# 800U-R3N3_LED_V1_2.net
KiCad netlist of a schematic drawn in Altium Designer
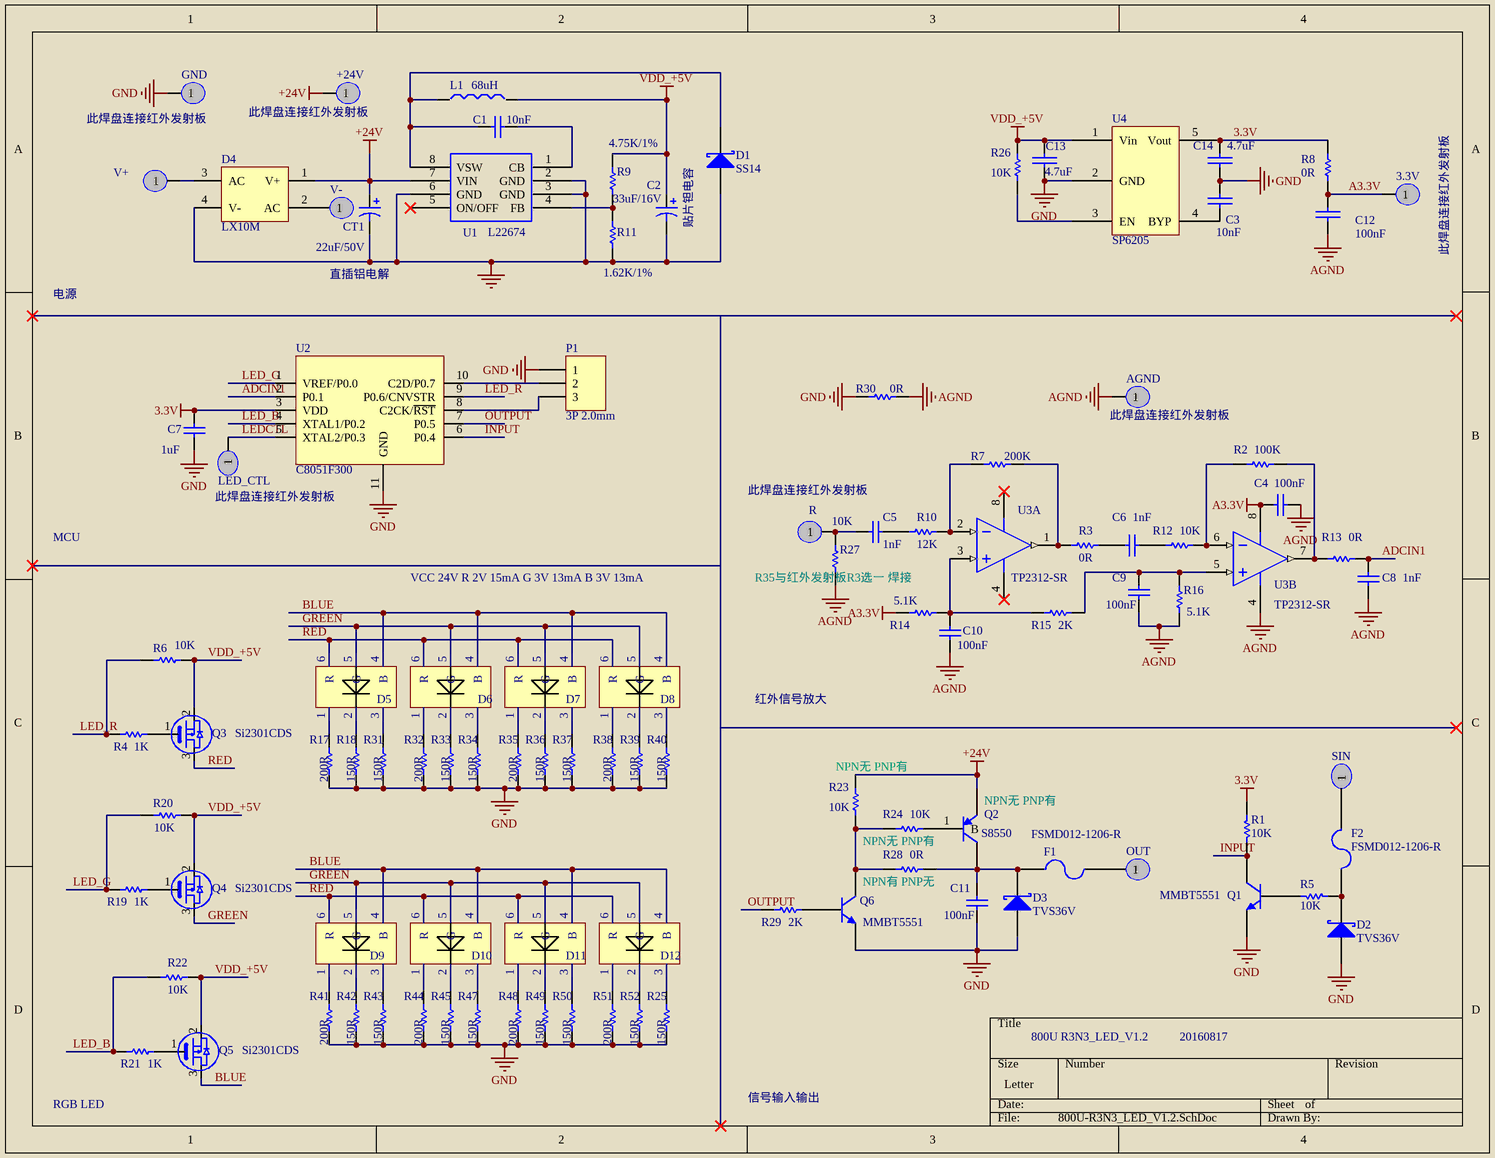
[diagram p0: 800U-R3N3_LED_V1.2.SchDoc]

(export (version "E")
  (design (tool "Eeschema 10.0.6"))
  (components
    (comp (ref "+24V")
      (value "~")
      (footprint "HOLE_SMD")
      (fields (field (name "ALTIUM_UNNAMED_1") "此焊盘连接红外发射板"))
      (libsource (lib "MODBUS_V1.0") (part "焊盘"))
    )
    (comp (ref "3.3V")
      (value "~")
      (footprint "HOLE_SMD")
      (fields (field (name "ALTIUM_UNNAMED_1") "此焊盘连接红外发射板"))
      (libsource (lib "MODBUS_V1.0") (part "焊盘"))
    )
    (comp (ref "AGND")
      (value "~")
      (footprint "HOLE_SMD")
      (fields (field (name "ALTIUM_UNNAMED_1") "此焊盘连接红外发射板"))
      (libsource (lib "MODBUS_V1.0") (part "焊盘"))
    )
    (comp (ref "C1")
      (value "10nF")
      (footprint "C0603")
      (description "Capacitor")
      (fields (field (name "PUBLISHER") "Altium Limited"))
      (libsource (lib "*") (part "Cap"))
    )
    (comp (ref "C2")
      (value "33uF/16V")
      (footprint "CT3528")
      (description "Polarized Capacitor (Radial)")
      (fields (field (name "KIND") "贴片钽电容"))
      (libsource (lib "*") (part "Cap Pol1"))
    )
    (comp (ref "C3")
      (value "10nF")
      (footprint "C0603")
      (description "Capacitor")
      (libsource (lib "*") (part "CAP"))
    )
    (comp (ref "C4")
      (value "100nF")
      (footprint "C0603")
      (description "Capacitor")
      (fields (field (name "PUBLISHER") "Altium Limited"))
      (libsource (lib "TMJD1.0") (part "Cap"))
    )
    (comp (ref "C5")
      (value "1nF")
      (footprint "C0603")
      (description "Capacitor")
      (fields (field (name "PUBLISHER") "Altium Limited"))
      (libsource (lib "TMJD1.0") (part "Cap"))
    )
    (comp (ref "C6")
      (value "1nF")
      (footprint "C0603")
      (description "Capacitor")
      (fields (field (name "PUBLISHER") "Altium Limited"))
      (libsource (lib "TMJD1.0") (part "Cap"))
    )
    (comp (ref "C7")
      (value "1uF")
      (footprint "C0603")
      (description "贴片电容")
      (fields (field (name "PUBLISHER") "Altium Limited"))
      (libsource (lib "TMJD1.0") (part "Cap"))
    )
    (comp (ref "C8")
      (value "1nF")
      (footprint "C0603")
      (description "Capacitor")
      (fields (field (name "PUBLISHER") "Altium Limited"))
      (libsource (lib "TMJD1.0") (part "Cap"))
    )
    (comp (ref "C9")
      (value "100nF")
      (footprint "C0603")
      (description "Capacitor")
      (fields (field (name "PUBLISHER") "Altium Limited"))
      (libsource (lib "TMJD1.0") (part "Cap"))
    )
    (comp (ref "C10")
      (value "100nF")
      (footprint "C0603")
      (description "Capacitor")
      (fields (field (name "PUBLISHER") "Altium Limited"))
      (libsource (lib "TMJD1.0") (part "Cap"))
    )
    (comp (ref "C11")
      (value "100nF")
      (footprint "C0603")
      (description "贴片电容")
      (fields (field (name "PUBLISHER") "Altium Limited"))
      (libsource (lib "TMJD1.0") (part "Cap"))
    )
    (comp (ref "C12")
      (value "100nF")
      (footprint "C0603")
      (description "Capacitor")
      (libsource (lib "*") (part "CAP"))
    )
    (comp (ref "C13")
      (value "4.7uF")
      (footprint "C0603")
      (description "Capacitor")
      (libsource (lib "*") (part "CAP"))
    )
    (comp (ref "C14")
      (value "4.7uF")
      (footprint "C0603")
      (description "Capacitor")
      (libsource (lib "*") (part "CAP"))
    )
    (comp (ref "CT1")
      (value "22uF/50V")
      (footprint "RB0.1")
      (description "Polarized Capacitor (Radial)")
      (fields (field (name "KIND") "直插铝电解"))
      (libsource (lib "*") (part "Cap Pol1"))
    )
    (comp (ref "D1") (value "SS14") (footprint "SMB") (libsource (lib "*") (part "SMBJ6.0CA")))
    (comp (ref "D2")
      (value "TVS36V")
      (footprint "HSMA")
      (description "贴片TVS")
      (fields (field (name "PUBLISHER") "Altium Limited"))
      (libsource (lib "*") (part "D Schottky"))
    )
    (comp (ref "D3")
      (value "TVS36V")
      (footprint "HSMA")
      (description "贴片TVS")
      (fields (field (name "PUBLISHER") "Altium Limited"))
      (libsource (lib "*") (part "D Schottky"))
    )
    (comp (ref "D4")
      (value "LX10M")
      (footprint "桥堆 3.8*3.5")
      (description "贴片桥堆")
      (libsource (lib "Miscellaneous Devices") (part "Bridge2"))
    )
    (comp (ref "D5")
      (value "5050RGB")
      (footprint "5050RGB")
      (description "RBG发光管")
      (libsource (lib "MODBUS_V1.0") (part "5050RGB"))
    )
    (comp (ref "D6")
      (value "5050RGB")
      (footprint "5050RGB")
      (description "RBG发光管")
      (libsource (lib "MODBUS_V1.0") (part "5050RGB"))
    )
    (comp (ref "D7")
      (value "5050RGB")
      (footprint "5050RGB")
      (description "RBG发光管")
      (libsource (lib "MODBUS_V1.0") (part "5050RGB"))
    )
    (comp (ref "D8")
      (value "5050RGB")
      (footprint "5050RGB")
      (description "RBG发光管")
      (libsource (lib "MODBUS_V1.0") (part "5050RGB"))
    )
    (comp (ref "D9")
      (value "5050RGB")
      (footprint "5050RGB")
      (description "RBG发光管")
      (libsource (lib "MODBUS_V1.0") (part "5050RGB"))
    )
    (comp (ref "D10")
      (value "5050RGB")
      (footprint "5050RGB")
      (description "RBG发光管")
      (libsource (lib "MODBUS_V1.0") (part "5050RGB"))
    )
    (comp (ref "D11")
      (value "5050RGB")
      (footprint "5050RGB")
      (description "RBG发光管")
      (libsource (lib "MODBUS_V1.0") (part "5050RGB"))
    )
    (comp (ref "D12")
      (value "5050RGB")
      (footprint "5050RGB")
      (description "RBG发光管")
      (libsource (lib "MODBUS_V1.0") (part "5050RGB"))
    )
    (comp (ref "F1")
      (value "FSMD012-1206-R")
      (footprint "1206")
      (description "Fuse")
      (libsource (lib "Miscellaneous Devices") (part "Fuse 2"))
    )
    (comp (ref "F2")
      (value "FSMD012-1206-R")
      (footprint "1206")
      (description "Fuse")
      (libsource (lib "") (part "Fuse 2_1"))
    )
    (comp (ref "GND")
      (value "~")
      (footprint "HOLE_SMD")
      (fields (field (name "ALTIUM_UNNAMED_1") "此焊盘连接红外发射板"))
      (libsource (lib "MODBUS_V1.0") (part "焊盘"))
    )
    (comp (ref "L1") (value "68uH") (footprint "L-6X6") (libsource (lib "*") (part "电感")))
    (comp (ref "LED_CTL")
      (value "~")
      (footprint "HOLE_SMD")
      (fields (field (name "ALTIUM_UNNAMED_1") "此焊盘连接红外发射板"))
      (libsource (lib "MODBUS_V1.0") (part "焊盘"))
    )
    (comp (ref "OUT") (value "~") (footprint "HOLE_SMD") (libsource (lib "MODBUS_V1.0") (part "焊盘")))
    (comp (ref "P1")
      (value "3P 2.0mm")
      (footprint "SIP3")
      (description "插座")
      (fields (field (name "PUBLISHER") "Altium Limited"))
      (libsource (lib "Miscellaneous Connectors") (part "MHDR1X3"))
    )
    (comp (ref "Q1")
      (value "MMBT5551")
      (footprint "SOT-23")
      (description "贴片NPN三极管")
      (libsource (lib "Miscellaneous Devices") (part "NPN"))
    )
    (comp (ref "Q2")
      (value "S8550")
      (footprint "SOT-23")
      (description "贴片PNP三极管")
      (fields (field (name "ALTIUM_UNNAMED_1") "NPN无 PNP有"))
      (libsource (lib "MODBUS_V1.0") (part "S8550"))
    )
    (comp (ref "Q3")
      (value "Si2301CDS")
      (footprint "SOT-23")
      (description "贴片MOS管")
      (libsource (lib "BATTERY") (part "P-MOSFET"))
    )
    (comp (ref "Q4")
      (value "Si2301CDS")
      (footprint "SOT-23")
      (description "贴片MOS管")
      (libsource (lib "BATTERY") (part "P-MOSFET"))
    )
    (comp (ref "Q5")
      (value "Si2301CDS")
      (footprint "SOT-23")
      (description "贴片MOS管")
      (libsource (lib "BATTERY") (part "P-MOSFET"))
    )
    (comp (ref "Q6")
      (value "MMBT5551")
      (footprint "SOT-23")
      (description "NPN三极管")
      (libsource (lib "Miscellaneous Devices") (part "NPN"))
    )
    (comp (ref "R")
      (value "~")
      (footprint "HOLE_SMD")
      (fields (field (name "ALTIUM_UNNAMED_1") "此焊盘连接红外发射板"))
      (libsource (lib "MODBUS_V1.0") (part "焊盘"))
    )
    (comp (ref "R1")
      (value "10K")
      (footprint "R0603")
      (description "贴片电阻")
      (libsource (lib "Miscellaneous Devices") (part "Res Semi"))
    )
    (comp (ref "R2")
      (value "100K")
      (footprint "R0603")
      (description "Semiconductor Resistor")
      (libsource (lib "Miscellaneous Devices") (part "Res Semi"))
    )
    (comp (ref "R3")
      (value "0R")
      (footprint "R0603")
      (description "Semiconductor Resistor")
      (libsource (lib "Miscellaneous Devices") (part "Res Semi"))
    )
    (comp (ref "R4")
      (value "1K")
      (footprint "R0603")
      (description "贴片电阻")
      (libsource (lib "Miscellaneous Devices") (part "Res Semi"))
    )
    (comp (ref "R5")
      (value "10K")
      (footprint "R0603")
      (description "贴片电阻")
      (libsource (lib "Miscellaneous Devices") (part "Res Semi"))
    )
    (comp (ref "R6")
      (value "10K")
      (footprint "R0603")
      (description "贴片电阻")
      (libsource (lib "Miscellaneous Devices") (part "Res Semi"))
    )
    (comp (ref "R7")
      (value "200K")
      (footprint "R0603")
      (description "Semiconductor Resistor")
      (libsource (lib "Miscellaneous Devices") (part "Res Semi"))
    )
    (comp (ref "R8")
      (value "0R")
      (footprint "R0603")
      (description "Resistor")
      (fields (field (name "PUBLISHER") "Altium Limited"))
      (libsource (lib "*") (part "Res1"))
    )
    (comp (ref "R9")
      (value "4.75K/1%")
      (footprint "R0603")
      (description "Semiconductor Resistor")
      (fields (field (name "PUBLISHER") "Altium Limited"))
      (libsource (lib "*") (part "Res Semi"))
    )
    (comp (ref "R10")
      (value "12K")
      (footprint "R0603")
      (description "Semiconductor Resistor")
      (libsource (lib "Miscellaneous Devices") (part "Res Semi"))
    )
    (comp (ref "R11")
      (value "1.62K/1%")
      (footprint "R0603")
      (description "Semiconductor Resistor")
      (fields (field (name "PUBLISHER") "Altium Limited"))
      (libsource (lib "*") (part "Res Semi"))
    )
    (comp (ref "R12")
      (value "10K")
      (footprint "R0603")
      (description "Semiconductor Resistor")
      (libsource (lib "Miscellaneous Devices") (part "Res Semi"))
    )
    (comp (ref "R13")
      (value "0R")
      (footprint "R0603")
      (description "Semiconductor Resistor")
      (libsource (lib "Miscellaneous Devices") (part "Res Semi"))
    )
    (comp (ref "R14")
      (value "5.1K")
      (footprint "R0603")
      (description "Semiconductor Resistor")
      (libsource (lib "Miscellaneous Devices") (part "Res Semi"))
    )
    (comp (ref "R15")
      (value "2K")
      (footprint "R0603")
      (description "Semiconductor Resistor")
      (libsource (lib "Miscellaneous Devices") (part "Res Semi"))
    )
    (comp (ref "R16")
      (value "5.1K")
      (footprint "R0603")
      (description "Semiconductor Resistor")
      (libsource (lib "Miscellaneous Devices") (part "Res Semi"))
    )
    (comp (ref "R17")
      (value "200R")
      (footprint "0805")
      (description "贴片电阻")
      (libsource (lib "Miscellaneous Devices") (part "Res Semi"))
    )
    (comp (ref "R18")
      (value "150R")
      (footprint "0805")
      (description "贴片电阻")
      (libsource (lib "Miscellaneous Devices") (part "Res Semi"))
    )
    (comp (ref "R19")
      (value "1K")
      (footprint "R0603")
      (description "贴片电阻")
      (libsource (lib "Miscellaneous Devices") (part "Res Semi"))
    )
    (comp (ref "R20")
      (value "10K")
      (footprint "R0603")
      (description "贴片电阻")
      (libsource (lib "Miscellaneous Devices") (part "Res Semi"))
    )
    (comp (ref "R21")
      (value "1K")
      (footprint "R0603")
      (description "贴片电阻")
      (libsource (lib "Miscellaneous Devices") (part "Res Semi"))
    )
    (comp (ref "R22")
      (value "10K")
      (footprint "R0603")
      (description "贴片电阻")
      (libsource (lib "Miscellaneous Devices") (part "Res Semi"))
    )
    (comp (ref "R23")
      (value "10K")
      (footprint "R0603")
      (description "贴片电阻")
      (fields (field (name "ALTIUM_UNNAMED_1") "NPN无 PNP有"))
      (libsource (lib "Miscellaneous Devices") (part "Res Semi"))
    )
    (comp (ref "R24")
      (value "10K")
      (footprint "R0603")
      (description "贴片电阻")
      (fields (field (name "ALTIUM_UNNAMED_1") "NPN无 PNP有"))
      (libsource (lib "Miscellaneous Devices") (part "Res Semi"))
    )
    (comp (ref "R25")
      (value "150R")
      (footprint "0805")
      (description "贴片电阻")
      (libsource (lib "Miscellaneous Devices") (part "Res Semi"))
    )
    (comp (ref "R26")
      (value "10K")
      (footprint "R0603")
      (description "Resistor")
      (fields (field (name "PUBLISHER") "Altium Limited"))
      (libsource (lib "*") (part "Res1"))
    )
    (comp (ref "R27")
      (value "10K")
      (footprint "R0603")
      (description "Semiconductor Resistor")
      (fields (field (name "ALTIUM_UNNAMED_1") "R35与红外发射板R3选一 焊接"))
      (libsource (lib "Miscellaneous Devices") (part "Res Semi"))
    )
    (comp (ref "R28")
      (value "0R")
      (footprint "R0603")
      (description "贴片电阻")
      (fields (field (name "ALTIUM_UNNAMED_1") "NPN有 PNP无"))
      (libsource (lib "Miscellaneous Devices") (part "Res Semi"))
    )
    (comp (ref "R29")
      (value "2K")
      (footprint "R0603")
      (description "贴片电阻")
      (libsource (lib "Miscellaneous Devices") (part "Res Semi"))
    )
    (comp (ref "R30")
      (value "0R")
      (footprint "R0603")
      (description "Semiconductor Resistor")
      (libsource (lib "Miscellaneous Devices") (part "Res Semi"))
    )
    (comp (ref "R31")
      (value "150R")
      (footprint "0805")
      (description "贴片电阻")
      (libsource (lib "Miscellaneous Devices") (part "Res Semi"))
    )
    (comp (ref "R32")
      (value "200R")
      (footprint "0805")
      (description "贴片电阻")
      (libsource (lib "Miscellaneous Devices") (part "Res Semi"))
    )
    (comp (ref "R33")
      (value "150R")
      (footprint "0805")
      (description "贴片电阻")
      (libsource (lib "Miscellaneous Devices") (part "Res Semi"))
    )
    (comp (ref "R34")
      (value "150R")
      (footprint "0805")
      (description "贴片电阻")
      (libsource (lib "Miscellaneous Devices") (part "Res Semi"))
    )
    (comp (ref "R35")
      (value "200R")
      (footprint "0805")
      (description "贴片电阻")
      (libsource (lib "Miscellaneous Devices") (part "Res Semi"))
    )
    (comp (ref "R36")
      (value "150R")
      (footprint "0805")
      (description "贴片电阻")
      (libsource (lib "Miscellaneous Devices") (part "Res Semi"))
    )
    (comp (ref "R37")
      (value "150R")
      (footprint "0805")
      (description "贴片电阻")
      (libsource (lib "Miscellaneous Devices") (part "Res Semi"))
    )
    (comp (ref "R38")
      (value "200R")
      (footprint "0805")
      (description "贴片电阻")
      (libsource (lib "Miscellaneous Devices") (part "Res Semi"))
    )
    (comp (ref "R39")
      (value "150R")
      (footprint "0805")
      (description "贴片电阻")
      (libsource (lib "Miscellaneous Devices") (part "Res Semi"))
    )
    (comp (ref "R40")
      (value "150R")
      (footprint "0805")
      (description "贴片电阻")
      (libsource (lib "Miscellaneous Devices") (part "Res Semi"))
    )
    (comp (ref "R41")
      (value "200R")
      (footprint "MODBUS_V2.0:0805")
      (description "贴片电阻")
      (libsource (lib "Miscellaneous Devices") (part "Res Semi"))
    )
    (comp (ref "R42")
      (value "150R")
      (footprint "0805")
      (description "贴片电阻")
      (libsource (lib "Miscellaneous Devices") (part "Res Semi"))
    )
    (comp (ref "R43")
      (value "150R")
      (footprint "0805")
      (description "贴片电阻")
      (libsource (lib "Miscellaneous Devices") (part "Res Semi"))
    )
    (comp (ref "R44")
      (value "200R")
      (footprint "0805")
      (description "贴片电阻")
      (libsource (lib "Miscellaneous Devices") (part "Res Semi"))
    )
    (comp (ref "R45")
      (value "150R")
      (footprint "0805")
      (description "贴片电阻")
      (libsource (lib "Miscellaneous Devices") (part "Res Semi"))
    )
    (comp (ref "R47")
      (value "150R")
      (footprint "0805")
      (description "贴片电阻")
      (libsource (lib "Miscellaneous Devices") (part "Res Semi"))
    )
    (comp (ref "R48")
      (value "200R")
      (footprint "0805")
      (description "贴片电阻")
      (libsource (lib "Miscellaneous Devices") (part "Res Semi"))
    )
    (comp (ref "R49")
      (value "150R")
      (footprint "0805")
      (description "贴片电阻")
      (libsource (lib "Miscellaneous Devices") (part "Res Semi"))
    )
    (comp (ref "R50")
      (value "150R")
      (footprint "0805")
      (description "贴片电阻")
      (libsource (lib "Miscellaneous Devices") (part "Res Semi"))
    )
    (comp (ref "R51")
      (value "200R")
      (footprint "0805")
      (description "贴片电阻")
      (libsource (lib "Miscellaneous Devices") (part "Res Semi"))
    )
    (comp (ref "R52")
      (value "150R")
      (footprint "0805")
      (description "贴片电阻")
      (libsource (lib "Miscellaneous Devices") (part "Res Semi"))
    )
    (comp (ref "SIN") (value "~") (footprint "HOLE_SMD") (libsource (lib "MODBUS_V1.0") (part "焊盘")))
    (comp (ref "U1") (value "L22674") (footprint "SO-1.27-9/4.0") (libsource (lib "*") (part "2674")))
    (comp (ref "U2")
      (value "C8051F300")
      (footprint "QFN-11")
      (description "贴片芯片")
      (libsource (lib "集成块") (part "PIC16C505"))
    )
    (comp (ref "U3")
      (value "TP2312-SR")
      (footprint "SO-8")
      (description "Dual Low Noise, Audio Amplifier")
      (fields (field (name "PUBLISHER") "Altium Limited"))
      (libsource (lib "Motorola Amplifier Audio Amplifier") (part "LM833D"))
    )
    (comp (ref "U4")
      (value "SP6205")
      (footprint "SOT-23-5")
      (libsource (lib "MODBUS_V1.0") (part "SP6203/SP6205"))
    )
    (comp (ref "V+") (value "~") (footprint "HOLE_SMD") (libsource (lib "MODBUS_V1.0") (part "焊盘")))
    (comp (ref "V-") (value "~") (footprint "HOLE_SMD") (libsource (lib "MODBUS_V1.0") (part "焊盘")))
  )
  (nets
    (net (code "1") (name "+24V") (class "Default")
      (node (ref "+24V") (pin "1") (pinfunction "1_1") (pintype "passive"))
      (node (ref "CT1") (pin "1") (pinfunction "1_1") (pintype "passive"))
      (node (ref "D4") (pin "1") (pinfunction "V+_1") (pintype "passive"))
      (node (ref "Q2") (pin "2") (pinfunction "E_2") (pintype "passive"))
      (node (ref "R23") (pin "2") (pinfunction "2_2") (pintype "passive"))
      (node (ref "U1") (pin "7") (pinfunction "VIN_7") (pintype "passive"))
    )
    (net (code "2") (name "/ADCIN1") (class "Default")
      (node (ref "C8") (pin "2") (pinfunction "2_2") (pintype "passive"))
      (node (ref "R13") (pin "2") (pinfunction "2_2") (pintype "passive"))
      (node (ref "U2") (pin "2") (pinfunction "P0.1_2") (pintype "passive"))
    )
    (net (code "3") (name "/BLUE") (class "Default")
      (node (ref "D10") (pin "4") (pinfunction "B_4") (pintype "passive"))
      (node (ref "D11") (pin "4") (pinfunction "B_4") (pintype "passive"))
      (node (ref "D12") (pin "4") (pinfunction "B_4") (pintype "passive"))
      (node (ref "D5") (pin "4") (pinfunction "B_4") (pintype "passive"))
      (node (ref "D6") (pin "4") (pinfunction "B_4") (pintype "passive"))
      (node (ref "D7") (pin "4") (pinfunction "B_4") (pintype "passive"))
      (node (ref "D8") (pin "4") (pinfunction "B_4") (pintype "passive"))
      (node (ref "D9") (pin "4") (pinfunction "B_4") (pintype "passive"))
      (node (ref "Q5") (pin "3") (pinfunction "D_3") (pintype "passive"))
    )
    (net (code "4") (name "/GREEN") (class "Default")
      (node (ref "D10") (pin "5") (pinfunction "G_5") (pintype "passive"))
      (node (ref "D11") (pin "5") (pinfunction "G_5") (pintype "passive"))
      (node (ref "D12") (pin "5") (pinfunction "G_5") (pintype "passive"))
      (node (ref "D5") (pin "5") (pinfunction "G_5") (pintype "passive"))
      (node (ref "D6") (pin "5") (pinfunction "G_5") (pintype "passive"))
      (node (ref "D7") (pin "5") (pinfunction "G_5") (pintype "passive"))
      (node (ref "D8") (pin "5") (pinfunction "G_5") (pintype "passive"))
      (node (ref "D9") (pin "5") (pinfunction "G_5") (pintype "passive"))
      (node (ref "Q4") (pin "3") (pinfunction "D_3") (pintype "passive"))
    )
    (net (code "5") (name "/INPUT") (class "Default")
      (node (ref "Q1") (pin "3") (pinfunction "C_3") (pintype "passive"))
      (node (ref "R1") (pin "1") (pinfunction "1_1") (pintype "passive"))
      (node (ref "U2") (pin "6") (pinfunction "P0.4_6") (pintype "passive"))
    )
    (net (code "6") (name "/LEDCTL") (class "Default")
      (node (ref "LED_CTL") (pin "1") (pinfunction "1_1") (pintype "passive"))
      (node (ref "U2") (pin "5") (pinfunction "XTAL2/P0.3_5") (pintype "passive"))
    )
    (net (code "7") (name "/LED_B") (class "Default")
      (node (ref "R21") (pin "2") (pinfunction "2_2") (pintype "passive"))
      (node (ref "R22") (pin "2") (pinfunction "2_2") (pintype "passive"))
      (node (ref "U2") (pin "4") (pinfunction "XTAL1/P0.2_4") (pintype "passive"))
    )
    (net (code "8") (name "/LED_G") (class "Default")
      (node (ref "R19") (pin "2") (pinfunction "2_2") (pintype "passive"))
      (node (ref "R20") (pin "2") (pinfunction "2_2") (pintype "passive"))
      (node (ref "U2") (pin "1") (pinfunction "VREF/P0.0_1") (pintype "passive"))
    )
    (net (code "9") (name "/LED_R") (class "Default")
      (node (ref "R4") (pin "2") (pinfunction "2_2") (pintype "passive"))
      (node (ref "R6") (pin "2") (pinfunction "2_2") (pintype "passive"))
      (node (ref "U2") (pin "9") (pinfunction "P0.6/CNVSTR_9") (pintype "passive"))
    )
    (net (code "10") (name "/OUTPUT") (class "Default")
      (node (ref "R29") (pin "2") (pinfunction "2_2") (pintype "passive"))
      (node (ref "U2") (pin "7") (pinfunction "P0.5_7") (pintype "passive"))
    )
    (net (code "11") (name "/RED") (class "Default")
      (node (ref "D10") (pin "6") (pinfunction "R_6") (pintype "passive"))
      (node (ref "D11") (pin "6") (pinfunction "R_6") (pintype "passive"))
      (node (ref "D12") (pin "6") (pinfunction "R_6") (pintype "passive"))
      (node (ref "D5") (pin "6") (pinfunction "R_6") (pintype "passive"))
      (node (ref "D6") (pin "6") (pinfunction "R_6") (pintype "passive"))
      (node (ref "D7") (pin "6") (pinfunction "R_6") (pintype "passive"))
      (node (ref "D8") (pin "6") (pinfunction "R_6") (pintype "passive"))
      (node (ref "D9") (pin "6") (pinfunction "R_6") (pintype "passive"))
      (node (ref "Q3") (pin "3") (pinfunction "D_3") (pintype "passive"))
    )
    (net (code "12") (name "3.3V") (class "Default")
      (node (ref "C14") (pin "1") (pinfunction "1_1") (pintype "passive"))
      (node (ref "C7") (pin "1") (pinfunction "1_1") (pintype "passive"))
      (node (ref "R1") (pin "2") (pinfunction "2_2") (pintype "passive"))
      (node (ref "R8") (pin "1") (pinfunction "1_1") (pintype "passive"))
      (node (ref "U2") (pin "3") (pinfunction "VDD_3") (pintype "passive"))
      (node (ref "U4") (pin "5") (pinfunction "Vout_5") (pintype "passive"))
    )
    (net (code "13") (name "A3.3V") (class "Default")
      (node (ref "3.3V") (pin "1") (pinfunction "1_1") (pintype "passive"))
      (node (ref "C12") (pin "2") (pinfunction "2_2") (pintype "passive"))
      (node (ref "C4") (pin "1") (pinfunction "1_1") (pintype "passive"))
      (node (ref "R14") (pin "1") (pinfunction "1_1") (pintype "passive"))
      (node (ref "R8") (pin "2") (pinfunction "2_2") (pintype "passive"))
      (node (ref "U3") (pin "8") (pinfunction "VCC_8") (pintype "power_in"))
    )
    (net (code "14") (name "AGND") (class "Default")
      (node (ref "AGND") (pin "1") (pinfunction "1_1") (pintype "passive"))
      (node (ref "C10") (pin "2") (pinfunction "2_2") (pintype "passive"))
      (node (ref "C12") (pin "1") (pinfunction "1_1") (pintype "passive"))
      (node (ref "C4") (pin "2") (pinfunction "2_2") (pintype "passive"))
      (node (ref "C8") (pin "1") (pinfunction "1_1") (pintype "passive"))
      (node (ref "C9") (pin "2") (pinfunction "2_2") (pintype "passive"))
      (node (ref "R16") (pin "1") (pinfunction "1_1") (pintype "passive"))
      (node (ref "R27") (pin "2") (pinfunction "2_2") (pintype "passive"))
      (node (ref "R30") (pin "2") (pinfunction "2_2") (pintype "passive"))
      (node (ref "U3") (pin "4") (pinfunction "VEE_4") (pintype "power_in"))
    )
    (net (code "15") (name "GND") (class "Default")
      (node (ref "C11") (pin "2") (pinfunction "2_2") (pintype "passive"))
      (node (ref "C13") (pin "2") (pinfunction "2_2") (pintype "passive"))
      (node (ref "C14") (pin "2") (pinfunction "2_2") (pintype "passive"))
      (node (ref "C2") (pin "2") (pinfunction "2_2") (pintype "passive"))
      (node (ref "C3") (pin "2") (pinfunction "2_2") (pintype "passive"))
      (node (ref "C7") (pin "2") (pinfunction "2_2") (pintype "passive"))
      (node (ref "CT1") (pin "2") (pinfunction "2_2") (pintype "passive"))
      (node (ref "D1") (pin "1") (pinfunction "A_1") (pintype "passive"))
      (node (ref "D2") (pin "1") (pinfunction "A_1") (pintype "passive"))
      (node (ref "D3") (pin "1") (pinfunction "A_1") (pintype "passive"))
      (node (ref "D4") (pin "4") (pinfunction "V-_4") (pintype "passive"))
      (node (ref "GND") (pin "1") (pinfunction "1_1") (pintype "passive"))
      (node (ref "P1") (pin "1") (pinfunction "1_1") (pintype "passive"))
      (node (ref "Q1") (pin "2") (pinfunction "E_2") (pintype "passive"))
      (node (ref "Q6") (pin "2") (pinfunction "E_2") (pintype "passive"))
      (node (ref "R11") (pin "1") (pinfunction "1_1") (pintype "passive"))
      (node (ref "R17") (pin "1") (pinfunction "1_1") (pintype "passive"))
      (node (ref "R18") (pin "1") (pinfunction "1_1") (pintype "passive"))
      (node (ref "R25") (pin "1") (pinfunction "1_1") (pintype "passive"))
      (node (ref "R30") (pin "1") (pinfunction "1_1") (pintype "passive"))
      (node (ref "R31") (pin "1") (pinfunction "1_1") (pintype "passive"))
      (node (ref "R32") (pin "1") (pinfunction "1_1") (pintype "passive"))
      (node (ref "R33") (pin "1") (pinfunction "1_1") (pintype "passive"))
      (node (ref "R34") (pin "1") (pinfunction "1_1") (pintype "passive"))
      (node (ref "R35") (pin "1") (pinfunction "1_1") (pintype "passive"))
      (node (ref "R36") (pin "1") (pinfunction "1_1") (pintype "passive"))
      (node (ref "R37") (pin "1") (pinfunction "1_1") (pintype "passive"))
      (node (ref "R38") (pin "1") (pinfunction "1_1") (pintype "passive"))
      (node (ref "R39") (pin "1") (pinfunction "1_1") (pintype "passive"))
      (node (ref "R40") (pin "1") (pinfunction "1_1") (pintype "passive"))
      (node (ref "R41") (pin "1") (pinfunction "1_1") (pintype "passive"))
      (node (ref "R42") (pin "1") (pinfunction "1_1") (pintype "passive"))
      (node (ref "R43") (pin "1") (pinfunction "1_1") (pintype "passive"))
      (node (ref "R44") (pin "1") (pinfunction "1_1") (pintype "passive"))
      (node (ref "R45") (pin "1") (pinfunction "1_1") (pintype "passive"))
      (node (ref "R47") (pin "1") (pinfunction "1_1") (pintype "passive"))
      (node (ref "R48") (pin "1") (pinfunction "1_1") (pintype "passive"))
      (node (ref "R49") (pin "1") (pinfunction "1_1") (pintype "passive"))
      (node (ref "R50") (pin "1") (pinfunction "1_1") (pintype "passive"))
      (node (ref "R51") (pin "1") (pinfunction "1_1") (pintype "passive"))
      (node (ref "R52") (pin "1") (pinfunction "1_1") (pintype "passive"))
      (node (ref "U1") (pin "2") (pinfunction "GND_2") (pintype "passive"))
      (node (ref "U1") (pin "3") (pinfunction "GND_3") (pintype "passive"))
      (node (ref "U1") (pin "6") (pinfunction "GND_6") (pintype "passive"))
      (node (ref "U2") (pin "11") (pinfunction "GND_11") (pintype "passive"))
      (node (ref "U4") (pin "2") (pinfunction "GND_2") (pintype "passive"))
    )
    (net (code "16") (name "Net-(C5-Pad1)") (class "Default")
      (node (ref "C5") (pin "1") (pinfunction "1_1") (pintype "passive"))
      (node (ref "R") (pin "1") (pinfunction "1_1") (pintype "passive"))
      (node (ref "R27") (pin "1") (pinfunction "1_1") (pintype "passive"))
    )
    (net (code "17") (name "Net-(C5-Pad2)") (class "Default")
      (node (ref "C5") (pin "2") (pinfunction "2_2") (pintype "passive"))
      (node (ref "R10") (pin "1") (pinfunction "1_1") (pintype "passive"))
    )
    (net (code "18") (name "Net-(C6-Pad1)") (class "Default")
      (node (ref "C6") (pin "1") (pinfunction "1_1") (pintype "passive"))
      (node (ref "R3") (pin "2") (pinfunction "2_2") (pintype "passive"))
    )
    (net (code "19") (name "Net-(C6-Pad2)") (class "Default")
      (node (ref "C6") (pin "2") (pinfunction "2_2") (pintype "passive"))
      (node (ref "R12") (pin "1") (pinfunction "1_1") (pintype "passive"))
    )
    (net (code "20") (name "Net-(D1-K)") (class "Default")
      (node (ref "C1") (pin "2") (pinfunction "2_2") (pintype "passive"))
      (node (ref "D1") (pin "2") (pinfunction "K_2") (pintype "passive"))
      (node (ref "L1") (pin "1") (pinfunction "1_1") (pintype "passive"))
      (node (ref "U1") (pin "8") (pinfunction "VSW_8") (pintype "passive"))
    )
    (net (code "21") (name "Net-(D2-K)") (class "Default")
      (node (ref "D2") (pin "2") (pinfunction "K_2") (pintype "passive"))
      (node (ref "F2") (pin "1") (pinfunction "1_1") (pintype "passive"))
      (node (ref "R5") (pin "1") (pinfunction "1_1") (pintype "passive"))
    )
    (net (code "22") (name "Net-(D3-K)") (class "Default")
      (node (ref "C11") (pin "1") (pinfunction "1_1") (pintype "passive"))
      (node (ref "D3") (pin "2") (pinfunction "K_2") (pintype "passive"))
      (node (ref "F1") (pin "2") (pinfunction "2_2") (pintype "passive"))
      (node (ref "Q2") (pin "3") (pinfunction "C_3") (pintype "passive"))
      (node (ref "R28") (pin "2") (pinfunction "2_2") (pintype "passive"))
    )
    (net (code "23") (name "Net-(D4-AC-Pad2)") (class "Default")
      (node (ref "D4") (pin "2") (pinfunction "AC_2") (pintype "passive"))
      (node (ref "V-") (pin "1") (pinfunction "1_1") (pintype "passive"))
    )
    (net (code "24") (name "Net-(D4-AC-Pad3)") (class "Default")
      (node (ref "D4") (pin "3") (pinfunction "AC_3") (pintype "passive"))
      (node (ref "V+") (pin "1") (pinfunction "1_1") (pintype "passive"))
    )
    (net (code "25") (name "Net-(D5-Pad1)") (class "Default")
      (node (ref "D5") (pin "1") (pintype "passive"))
      (node (ref "R17") (pin "2") (pinfunction "2_2") (pintype "passive"))
    )
    (net (code "26") (name "Net-(D5-Pad2)") (class "Default")
      (node (ref "D5") (pin "2") (pintype "passive"))
      (node (ref "R18") (pin "2") (pinfunction "2_2") (pintype "passive"))
    )
    (net (code "27") (name "Net-(D5-Pad3)") (class "Default")
      (node (ref "D5") (pin "3") (pintype "passive"))
      (node (ref "R31") (pin "2") (pinfunction "2_2") (pintype "passive"))
    )
    (net (code "28") (name "Net-(D6-Pad1)") (class "Default")
      (node (ref "D6") (pin "1") (pintype "passive"))
      (node (ref "R32") (pin "2") (pinfunction "2_2") (pintype "passive"))
    )
    (net (code "29") (name "Net-(D6-Pad2)") (class "Default")
      (node (ref "D6") (pin "2") (pintype "passive"))
      (node (ref "R33") (pin "2") (pinfunction "2_2") (pintype "passive"))
    )
    (net (code "30") (name "Net-(D6-Pad3)") (class "Default")
      (node (ref "D6") (pin "3") (pintype "passive"))
      (node (ref "R34") (pin "2") (pinfunction "2_2") (pintype "passive"))
    )
    (net (code "31") (name "Net-(D7-Pad1)") (class "Default")
      (node (ref "D7") (pin "1") (pintype "passive"))
      (node (ref "R35") (pin "2") (pinfunction "2_2") (pintype "passive"))
    )
    (net (code "32") (name "Net-(D7-Pad2)") (class "Default")
      (node (ref "D7") (pin "2") (pintype "passive"))
      (node (ref "R36") (pin "2") (pinfunction "2_2") (pintype "passive"))
    )
    (net (code "33") (name "Net-(D7-Pad3)") (class "Default")
      (node (ref "D7") (pin "3") (pintype "passive"))
      (node (ref "R37") (pin "2") (pinfunction "2_2") (pintype "passive"))
    )
    (net (code "34") (name "Net-(D8-Pad1)") (class "Default")
      (node (ref "D8") (pin "1") (pintype "passive"))
      (node (ref "R38") (pin "2") (pinfunction "2_2") (pintype "passive"))
    )
    (net (code "35") (name "Net-(D8-Pad2)") (class "Default")
      (node (ref "D8") (pin "2") (pintype "passive"))
      (node (ref "R39") (pin "2") (pinfunction "2_2") (pintype "passive"))
    )
    (net (code "36") (name "Net-(D8-Pad3)") (class "Default")
      (node (ref "D8") (pin "3") (pintype "passive"))
      (node (ref "R40") (pin "2") (pinfunction "2_2") (pintype "passive"))
    )
    (net (code "37") (name "Net-(D9-Pad1)") (class "Default")
      (node (ref "D9") (pin "1") (pintype "passive"))
      (node (ref "R41") (pin "2") (pinfunction "2_2") (pintype "passive"))
    )
    (net (code "38") (name "Net-(D9-Pad2)") (class "Default")
      (node (ref "D9") (pin "2") (pintype "passive"))
      (node (ref "R42") (pin "2") (pinfunction "2_2") (pintype "passive"))
    )
    (net (code "39") (name "Net-(D9-Pad3)") (class "Default")
      (node (ref "D9") (pin "3") (pintype "passive"))
      (node (ref "R43") (pin "2") (pinfunction "2_2") (pintype "passive"))
    )
    (net (code "40") (name "Net-(D10-Pad1)") (class "Default")
      (node (ref "D10") (pin "1") (pintype "passive"))
      (node (ref "R44") (pin "2") (pinfunction "2_2") (pintype "passive"))
    )
    (net (code "41") (name "Net-(D10-Pad2)") (class "Default")
      (node (ref "D10") (pin "2") (pintype "passive"))
      (node (ref "R45") (pin "2") (pinfunction "2_2") (pintype "passive"))
    )
    (net (code "42") (name "Net-(D10-Pad3)") (class "Default")
      (node (ref "D10") (pin "3") (pintype "passive"))
      (node (ref "R47") (pin "2") (pinfunction "2_2") (pintype "passive"))
    )
    (net (code "43") (name "Net-(D11-Pad1)") (class "Default")
      (node (ref "D11") (pin "1") (pintype "passive"))
      (node (ref "R48") (pin "2") (pinfunction "2_2") (pintype "passive"))
    )
    (net (code "44") (name "Net-(D11-Pad2)") (class "Default")
      (node (ref "D11") (pin "2") (pintype "passive"))
      (node (ref "R49") (pin "2") (pinfunction "2_2") (pintype "passive"))
    )
    (net (code "45") (name "Net-(D11-Pad3)") (class "Default")
      (node (ref "D11") (pin "3") (pintype "passive"))
      (node (ref "R50") (pin "2") (pinfunction "2_2") (pintype "passive"))
    )
    (net (code "46") (name "Net-(D12-Pad1)") (class "Default")
      (node (ref "D12") (pin "1") (pintype "passive"))
      (node (ref "R51") (pin "2") (pinfunction "2_2") (pintype "passive"))
    )
    (net (code "47") (name "Net-(D12-Pad2)") (class "Default")
      (node (ref "D12") (pin "2") (pintype "passive"))
      (node (ref "R52") (pin "2") (pinfunction "2_2") (pintype "passive"))
    )
    (net (code "48") (name "Net-(D12-Pad3)") (class "Default")
      (node (ref "D12") (pin "3") (pintype "passive"))
      (node (ref "R25") (pin "2") (pinfunction "2_2") (pintype "passive"))
    )
    (net (code "49") (name "Net-(F1-Pad1)") (class "Default")
      (node (ref "F1") (pin "1") (pinfunction "1_1") (pintype "passive"))
      (node (ref "OUT") (pin "1") (pinfunction "1_1") (pintype "passive"))
    )
    (net (code "50") (name "Net-(F2-Pad2)") (class "Default")
      (node (ref "F2") (pin "2") (pinfunction "2_2") (pintype "passive"))
      (node (ref "SIN") (pin "1") (pinfunction "1_1") (pintype "passive"))
    )
    (net (code "51") (name "Net-(Q1-B)") (class "Default")
      (node (ref "Q1") (pin "1") (pinfunction "B_1") (pintype "passive"))
      (node (ref "R5") (pin "2") (pinfunction "2_2") (pintype "passive"))
    )
    (net (code "52") (name "Net-(Q2-B)") (class "Default")
      (node (ref "Q2") (pin "1") (pinfunction "B_1") (pintype "passive"))
      (node (ref "R24") (pin "2") (pinfunction "2_2") (pintype "passive"))
    )
    (net (code "53") (name "Net-(Q3-G)") (class "Default")
      (node (ref "Q3") (pin "1") (pinfunction "G_1") (pintype "passive"))
      (node (ref "R4") (pin "1") (pinfunction "1_1") (pintype "passive"))
    )
    (net (code "54") (name "Net-(Q4-G)") (class "Default")
      (node (ref "Q4") (pin "1") (pinfunction "G_1") (pintype "passive"))
      (node (ref "R19") (pin "1") (pinfunction "1_1") (pintype "passive"))
    )
    (net (code "55") (name "Net-(Q5-G)") (class "Default")
      (node (ref "Q5") (pin "1") (pinfunction "G_1") (pintype "passive"))
      (node (ref "R21") (pin "1") (pinfunction "1_1") (pintype "passive"))
    )
    (net (code "56") (name "Net-(Q6-B)") (class "Default")
      (node (ref "Q6") (pin "1") (pinfunction "B_1") (pintype "passive"))
      (node (ref "R29") (pin "1") (pinfunction "1_1") (pintype "passive"))
    )
    (net (code "57") (name "Net-(Q6-C)") (class "Default")
      (node (ref "Q6") (pin "3") (pinfunction "C_3") (pintype "passive"))
      (node (ref "R23") (pin "1") (pinfunction "1_1") (pintype "passive"))
      (node (ref "R24") (pin "1") (pinfunction "1_1") (pintype "passive"))
      (node (ref "R28") (pin "1") (pinfunction "1_1") (pintype "passive"))
    )
    (net (code "58") (name "Net-(U1-CB)") (class "Default")
      (node (ref "C1") (pin "1") (pinfunction "1_1") (pintype "passive"))
      (node (ref "U1") (pin "1") (pinfunction "CB_1") (pintype "passive"))
    )
    (net (code "59") (name "Net-(U1-FB)") (class "Default")
      (node (ref "R11") (pin "2") (pinfunction "2_2") (pintype "passive"))
      (node (ref "R9") (pin "1") (pinfunction "1_1") (pintype "passive"))
      (node (ref "U1") (pin "4") (pinfunction "FB_4") (pintype "passive"))
    )
    (net (code "60") (name "Net-(U2-C2CK{slash}~{RST})") (class "Default")
      (node (ref "P1") (pin "3") (pinfunction "3_3") (pintype "passive"))
      (node (ref "U2") (pin "8") (pinfunction "C2CK/~{RST}_8") (pintype "passive"))
    )
    (net (code "61") (name "Net-(U2-C2D{slash}P0.7)") (class "Default")
      (node (ref "P1") (pin "2") (pinfunction "2_2") (pintype "passive"))
      (node (ref "U2") (pin "10") (pinfunction "C2D/P0.7_10") (pintype "passive"))
    )
    (net (code "62") (name "Net-(U3A-IN+)") (class "Default")
      (node (ref "C10") (pin "1") (pinfunction "1_1") (pintype "passive"))
      (node (ref "R14") (pin "2") (pinfunction "2_2") (pintype "passive"))
      (node (ref "R15") (pin "1") (pinfunction "1_1") (pintype "passive"))
      (node (ref "U3") (pin "3") (pinfunction "IN+_3") (pintype "input"))
    )
    (net (code "63") (name "Net-(U3A-IN-)") (class "Default")
      (node (ref "R10") (pin "2") (pinfunction "2_2") (pintype "passive"))
      (node (ref "R7") (pin "1") (pinfunction "1_1") (pintype "passive"))
      (node (ref "U3") (pin "2") (pinfunction "IN-_2") (pintype "input"))
    )
    (net (code "64") (name "Net-(U3A-OUT)") (class "Default")
      (node (ref "R3") (pin "1") (pinfunction "1_1") (pintype "passive"))
      (node (ref "R7") (pin "2") (pinfunction "2_2") (pintype "passive"))
      (node (ref "U3") (pin "1") (pinfunction "OUT_1") (pintype "output"))
    )
    (net (code "65") (name "Net-(U3B-IN+)") (class "Default")
      (node (ref "C9") (pin "1") (pinfunction "1_1") (pintype "passive"))
      (node (ref "R15") (pin "2") (pinfunction "2_2") (pintype "passive"))
      (node (ref "R16") (pin "2") (pinfunction "2_2") (pintype "passive"))
      (node (ref "U3") (pin "5") (pinfunction "IN+_5") (pintype "input"))
    )
    (net (code "66") (name "Net-(U3B-IN-)") (class "Default")
      (node (ref "R12") (pin "2") (pinfunction "2_2") (pintype "passive"))
      (node (ref "R2") (pin "1") (pinfunction "1_1") (pintype "passive"))
      (node (ref "U3") (pin "6") (pinfunction "IN-_6") (pintype "input"))
    )
    (net (code "67") (name "Net-(U3B-OUT)") (class "Default")
      (node (ref "R13") (pin "1") (pinfunction "1_1") (pintype "passive"))
      (node (ref "R2") (pin "2") (pinfunction "2_2") (pintype "passive"))
      (node (ref "U3") (pin "7") (pinfunction "OUT_7") (pintype "output"))
    )
    (net (code "68") (name "Net-(U4-BYP)") (class "Default")
      (node (ref "C3") (pin "1") (pinfunction "1_1") (pintype "passive"))
      (node (ref "U4") (pin "4") (pinfunction "BYP_4") (pintype "passive"))
    )
    (net (code "69") (name "Net-(U4-EN)") (class "Default")
      (node (ref "R26") (pin "2") (pinfunction "2_2") (pintype "passive"))
      (node (ref "U4") (pin "3") (pinfunction "EN_3") (pintype "passive"))
    )
    (net (code "70") (name "VDD_+5V") (class "Default")
      (node (ref "C13") (pin "1") (pinfunction "1_1") (pintype "passive"))
      (node (ref "C2") (pin "1") (pinfunction "1_1") (pintype "passive"))
      (node (ref "L1") (pin "2") (pinfunction "2_2") (pintype "passive"))
      (node (ref "Q3") (pin "2") (pinfunction "S_2") (pintype "passive"))
      (node (ref "Q4") (pin "2") (pinfunction "S_2") (pintype "passive"))
      (node (ref "Q5") (pin "2") (pinfunction "S_2") (pintype "passive"))
      (node (ref "R20") (pin "1") (pinfunction "1_1") (pintype "passive"))
      (node (ref "R22") (pin "1") (pinfunction "1_1") (pintype "passive"))
      (node (ref "R26") (pin "1") (pinfunction "1_1") (pintype "passive"))
      (node (ref "R6") (pin "1") (pinfunction "1_1") (pintype "passive"))
      (node (ref "R9") (pin "2") (pinfunction "2_2") (pintype "passive"))
      (node (ref "U4") (pin "1") (pinfunction "Vin_1") (pintype "passive"))
    )
    (net (code "71") (name "unconnected-(U1-ON{slash}OFF-Pad5)") (class "Default")
      (node (ref "U1") (pin "5") (pinfunction "ON/OFF_5") (pintype "passive+no_connect"))
    )
    (net (code "72") (name "unconnected-(U3A-VCC-Pad8)") (class "Default")
      (node (ref "U3") (pin "8") (pinfunction "VCC_8") (pintype "power_in+no_connect"))
    )
    (net (code "73") (name "unconnected-(U3A-VEE-Pad4)") (class "Default")
      (node (ref "U3") (pin "4") (pinfunction "VEE_4") (pintype "power_in+no_connect"))
    )
  )
)
